# Capacitive-Touch-PCB.net
KiCad netlist of a schematic drawn in EAGLE
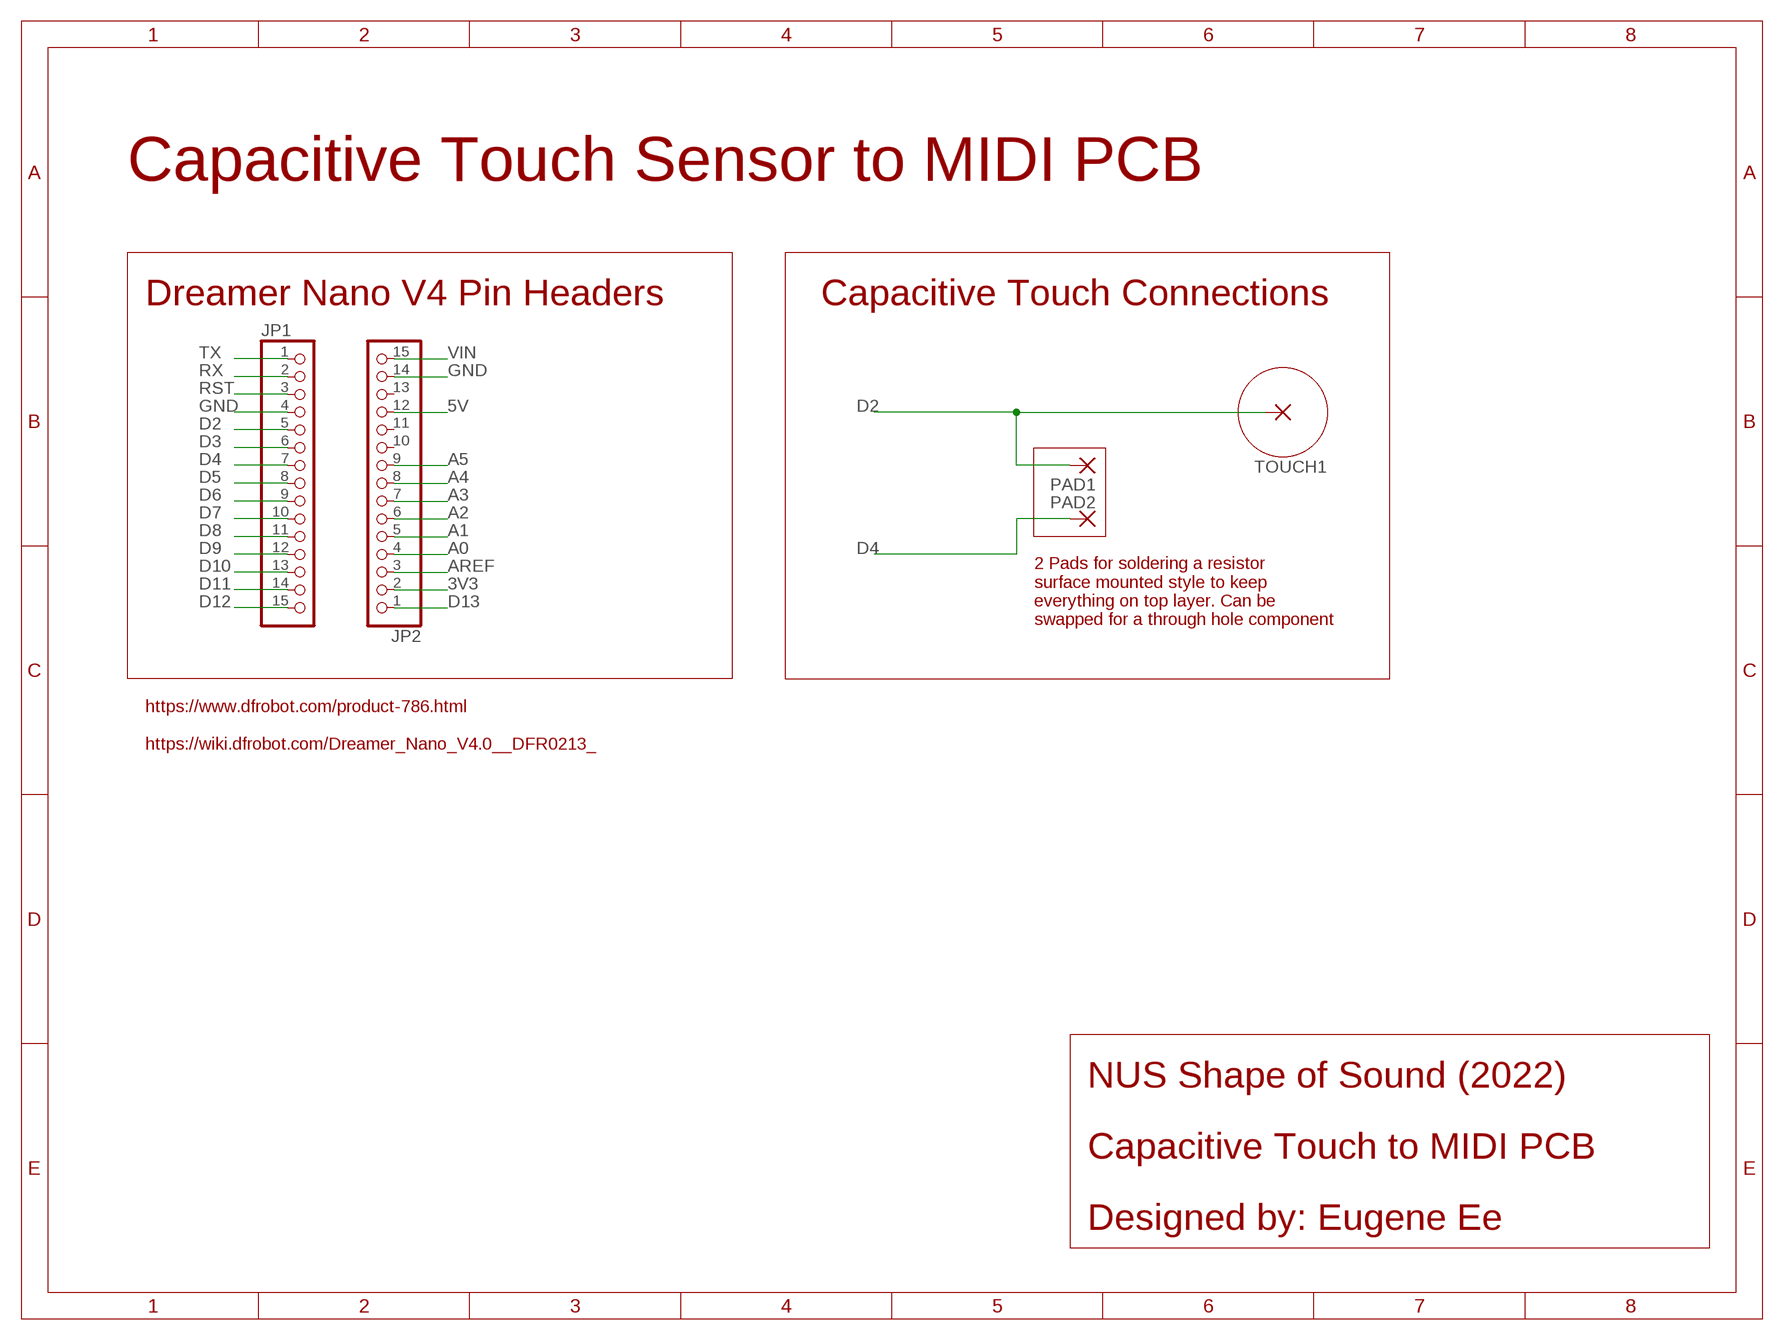
[diagram p0: schematic, sheet 1]

(export (version "E")
  (design (tool "Eeschema 10.0.6"))
  (components
    (comp (ref "JP1")
      (value "PINHD-1X15")
      (footprint "eagle-import:1X15")
      (libsource (lib "eagle-import") (part "PINHD-1X15"))
    )
    (comp (ref "JP2")
      (value "PINHD-1X15")
      (footprint "eagle-import:1X15")
      (libsource (lib "eagle-import") (part "PINHD-1X15"))
    )
    (comp (ref "PAD1")
      (value "SMD5")
      (footprint "eagle-import:SMD2,54-5,08")
      (libsource (lib "eagle-import") (part "SMD5"))
    )
    (comp (ref "PAD2")
      (value "SMD5")
      (footprint "eagle-import:SMD2,54-5,08")
      (libsource (lib "eagle-import") (part "SMD5"))
    )
    (comp (ref "TOUCH1")
      (value "SMD5")
      (footprint "eagle-import:SMD2,54-5,08")
      (libsource (lib "eagle-import") (part "SMD5"))
    )
  )
  (nets
    (net (code "1") (name "/3V3") (class "Default")
      (node (ref "JP2") (pin "2") (pinfunction "2_2") (pintype "passive"))
    )
    (net (code "2") (name "/5V") (class "Default")
      (node (ref "JP2") (pin "12") (pinfunction "12_12") (pintype "passive"))
    )
    (net (code "3") (name "/A0") (class "Default")
      (node (ref "JP2") (pin "4") (pinfunction "4_4") (pintype "passive"))
    )
    (net (code "4") (name "/A1") (class "Default")
      (node (ref "JP2") (pin "5") (pinfunction "5_5") (pintype "passive"))
    )
    (net (code "5") (name "/A2") (class "Default")
      (node (ref "JP2") (pin "6") (pinfunction "6_6") (pintype "passive"))
    )
    (net (code "6") (name "/A3") (class "Default")
      (node (ref "JP2") (pin "7") (pinfunction "7_7") (pintype "passive"))
    )
    (net (code "7") (name "/A4") (class "Default")
      (node (ref "JP2") (pin "8") (pinfunction "8_8") (pintype "passive"))
    )
    (net (code "8") (name "/A5") (class "Default")
      (node (ref "JP2") (pin "9") (pinfunction "9_9") (pintype "passive"))
    )
    (net (code "9") (name "/AREF") (class "Default")
      (node (ref "JP2") (pin "3") (pinfunction "3_3") (pintype "passive"))
    )
    (net (code "10") (name "/D2") (class "Default")
      (node (ref "JP1") (pin "5") (pinfunction "5_5") (pintype "passive"))
      (node (ref "PAD1") (pin "1") (pinfunction "P_1") (pintype "passive"))
      (node (ref "TOUCH1") (pin "1") (pinfunction "P_1") (pintype "passive"))
    )
    (net (code "11") (name "/D3") (class "Default")
      (node (ref "JP1") (pin "6") (pinfunction "6_6") (pintype "passive"))
    )
    (net (code "12") (name "/D4") (class "Default")
      (node (ref "JP1") (pin "7") (pinfunction "7_7") (pintype "passive"))
      (node (ref "PAD2") (pin "1") (pinfunction "P_1") (pintype "passive"))
    )
    (net (code "13") (name "/D5") (class "Default")
      (node (ref "JP1") (pin "8") (pinfunction "8_8") (pintype "passive"))
    )
    (net (code "14") (name "/D6") (class "Default")
      (node (ref "JP1") (pin "9") (pinfunction "9_9") (pintype "passive"))
    )
    (net (code "15") (name "/D7") (class "Default")
      (node (ref "JP1") (pin "10") (pinfunction "10_10") (pintype "passive"))
    )
    (net (code "16") (name "/D8") (class "Default")
      (node (ref "JP1") (pin "11") (pinfunction "11_11") (pintype "passive"))
    )
    (net (code "17") (name "/D9") (class "Default")
      (node (ref "JP1") (pin "12") (pinfunction "12_12") (pintype "passive"))
    )
    (net (code "18") (name "/D10") (class "Default")
      (node (ref "JP1") (pin "13") (pinfunction "13_13") (pintype "passive"))
    )
    (net (code "19") (name "/D11") (class "Default")
      (node (ref "JP1") (pin "14") (pinfunction "14_14") (pintype "passive"))
    )
    (net (code "20") (name "/D12") (class "Default")
      (node (ref "JP1") (pin "15") (pinfunction "15_15") (pintype "passive"))
    )
    (net (code "21") (name "/D13") (class "Default")
      (node (ref "JP2") (pin "1") (pinfunction "1_1") (pintype "passive"))
    )
    (net (code "22") (name "/GND") (class "Default")
      (node (ref "JP1") (pin "4") (pinfunction "4_4") (pintype "passive"))
      (node (ref "JP2") (pin "14") (pinfunction "14_14") (pintype "passive"))
    )
    (net (code "23") (name "/RST") (class "Default")
      (node (ref "JP1") (pin "3") (pinfunction "3_3") (pintype "passive"))
    )
    (net (code "24") (name "/RX") (class "Default")
      (node (ref "JP1") (pin "2") (pinfunction "2_2") (pintype "passive"))
    )
    (net (code "25") (name "/TX") (class "Default")
      (node (ref "JP1") (pin "1") (pinfunction "1_1") (pintype "passive"))
    )
    (net (code "26") (name "/VIN") (class "Default")
      (node (ref "JP2") (pin "15") (pinfunction "15_15") (pintype "passive"))
    )
    (net (code "27") (name "unconnected-(JP2-Pad10)") (class "Default")
      (node (ref "JP2") (pin "10") (pinfunction "10_10") (pintype "passive"))
    )
    (net (code "28") (name "unconnected-(JP2-Pad11)") (class "Default")
      (node (ref "JP2") (pin "11") (pinfunction "11_11") (pintype "passive"))
    )
    (net (code "29") (name "unconnected-(JP2-Pad13)") (class "Default")
      (node (ref "JP2") (pin "13") (pinfunction "13_13") (pintype "passive"))
    )
  )
)
